# Accelerometer.net
KiCad netlist of a schematic drawn in Altium Designer
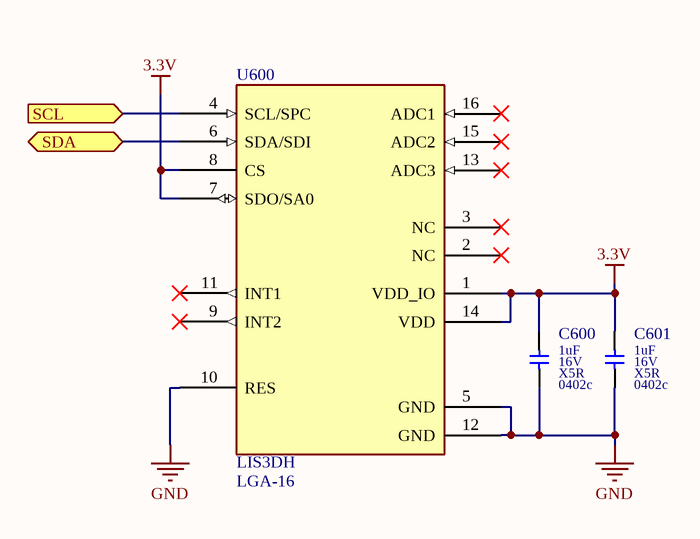
[diagram p0: Accelerometer.SchDoc]

(export (version "E")
  (design (tool "Eeschema 10.0.6"))
  (components
    (comp (ref "C600")
      (value "CL05A105KO5NNNC")
      (footprint "CAPC1005X60L")
      (description "SMT 0402c 1uF 16V 10% X5R 11.9MHz 85'C")
      (fields
        (field (name "11 PARAMETER 4") "X5R")
        (field (name "07 PACKAGE") "0402c")
        (field (name "08 PARAMETER 1") "1uF")
        (field (name "09 PARAMETER 2") "16V")
      )
      (libsource (lib "MS_Altium_Lib") (part "CAPACITOR"))
    )
    (comp (ref "C601")
      (value "CL05A105KO5NNNC")
      (footprint "CAPC1005X60L")
      (description "SMT 0402c 1uF 16V 10% X5R 11.9MHz 85'C")
      (fields
        (field (name "11 PARAMETER 4") "X5R")
        (field (name "07 PACKAGE") "0402c")
        (field (name "08 PARAMETER 1") "1uF")
        (field (name "09 PARAMETER 2") "16V")
      )
      (libsource (lib "MS_Altium_Lib") (part "CAPACITOR"))
    )
    (comp (ref "U600")
      (value "LIS3DH")
      (footprint "LGA16R50P5X3_300X300X100")
      (description "SMT LGA-16 ACCELEROMETER 1.71V - 3.6V +/- 16g")
      (fields (field (name "02 MPN") "LIS3DH") (field (name "07 PACKAGE") "LGA-16"))
      (libsource (lib "MS_Altium_Lib") (part "LIS3DH"))
    )
  )
  (nets
    (net (code "1") (name "/SCL") (class "Default")
      (node (ref "U600") (pin "4") (pinfunction "SCL/SPC_4") (pintype "input"))
    )
    (net (code "2") (name "/SDA") (class "Default")
      (node (ref "U600") (pin "6") (pinfunction "SDA/SDI_6") (pintype "input"))
    )
    (net (code "3") (name "3.3V") (class "Default")
      (node (ref "C600") (pin "2") (pinfunction "2_2") (pintype "passive"))
      (node (ref "C601") (pin "2") (pinfunction "2_2") (pintype "passive"))
      (node (ref "U600") (pin "1") (pinfunction "VDD_IO_1") (pintype "power_in"))
      (node (ref "U600") (pin "14") (pinfunction "VDD_14") (pintype "power_in"))
      (node (ref "U600") (pin "7") (pinfunction "SDO/SA0_7") (pintype "bidirectional"))
      (node (ref "U600") (pin "8") (pinfunction "CS_8") (pintype "passive"))
    )
    (net (code "4") (name "GND") (class "Default")
      (node (ref "C600") (pin "1") (pinfunction "1_1") (pintype "passive"))
      (node (ref "C601") (pin "1") (pinfunction "1_1") (pintype "passive"))
      (node (ref "U600") (pin "10") (pinfunction "RES_10") (pintype "passive"))
      (node (ref "U600") (pin "12") (pinfunction "GND_12") (pintype "power_in"))
      (node (ref "U600") (pin "5") (pinfunction "GND_5") (pintype "power_in"))
    )
    (net (code "5") (name "unconnected-(U600-ADC1-Pad16)") (class "Default")
      (node (ref "U600") (pin "16") (pinfunction "ADC1_16") (pintype "input+no_connect"))
    )
    (net (code "6") (name "unconnected-(U600-ADC2-Pad15)") (class "Default")
      (node (ref "U600") (pin "15") (pinfunction "ADC2_15") (pintype "input+no_connect"))
    )
    (net (code "7") (name "unconnected-(U600-ADC3-Pad13)") (class "Default")
      (node (ref "U600") (pin "13") (pinfunction "ADC3_13") (pintype "input+no_connect"))
    )
    (net (code "8") (name "unconnected-(U600-INT1-Pad11)") (class "Default")
      (node (ref "U600") (pin "11") (pinfunction "INT1_11") (pintype "output+no_connect"))
    )
    (net (code "9") (name "unconnected-(U600-INT2-Pad9)") (class "Default")
      (node (ref "U600") (pin "9") (pinfunction "INT2_9") (pintype "output+no_connect"))
    )
    (net (code "10") (name "unconnected-(U600-NC-Pad2)") (class "Default")
      (node (ref "U600") (pin "2") (pinfunction "NC_2") (pintype "passive+no_connect"))
    )
    (net (code "11") (name "unconnected-(U600-NC-Pad3)") (class "Default")
      (node (ref "U600") (pin "3") (pinfunction "NC_3") (pintype "passive+no_connect"))
    )
  )
)
